# Oscillator_16MHz.net
KiCad netlist of a schematic drawn in Altium Designer
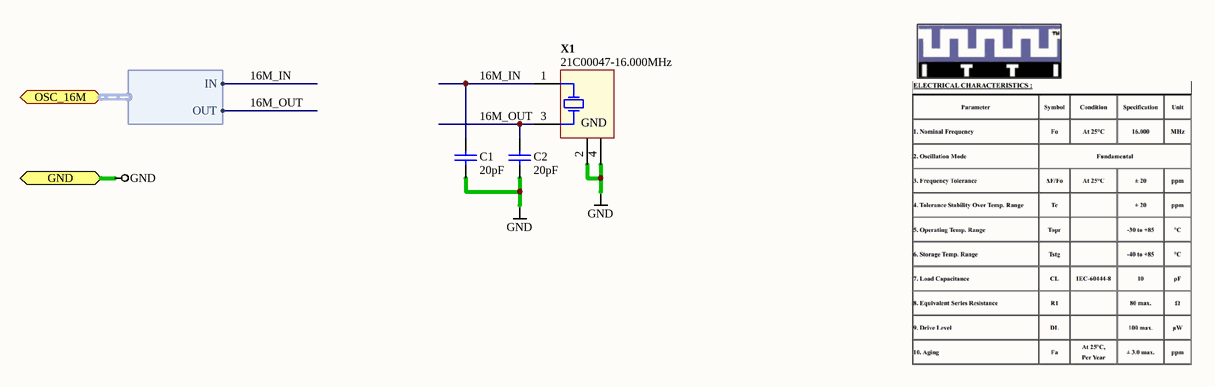
[diagram p0: Oscillator_16MHz.SchDoc]

(export (version "E")
  (design (tool "Eeschema 10.0.6"))
  (components
    (comp (ref "C1")
      (value "20pF")
      (footprint "CAPC0402(1005)60_N")
      (description "CAP 20pF 10V ±0.25pF 0402 (1005 Metric) Thickness 0.6mm SMD")
      (fields (field (name "TOLERANCE") "±0.25pF") (field (name "Comment") "CAP 20pF 10V 0402(1005)"))
      (libsource (lib "Altium Content Vault") (part "CMP-1034-00871-1"))
    )
    (comp (ref "C2")
      (value "20pF")
      (footprint "CAPC0402(1005)60_N")
      (description "CAP 20pF 10V ±0.25pF 0402 (1005 Metric) Thickness 0.6mm SMD")
      (fields (field (name "TOLERANCE") "±0.25pF") (field (name "Comment") "CAP 20pF 10V 0402(1005)"))
      (libsource (lib "Altium Content Vault") (part "CMP-1034-00871-1"))
    )
    (comp (ref "X1")
      (value "21C00047-16.000MHz")
      (footprint "ITTI-21C00047-16.000MHz-4_V")
      (description "Crystal, 16 MHz, -30 to 85 degC, 3.2 x 2.5 x 0.9 mm SMD")
      (fields (field (name "MANUFACTURER") "ITTI"))
      (libsource (lib "Altium Content Vault") (part "ITTI-21C00047-4"))
    )
  )
  (nets
    (net (code "2") (name "/16M_IN") (class "Default")
      (node (ref "C1") (pin "1") (pinfunction "1_1") (pintype "passive"))
      (node (ref "X1") (pin "1") (pinfunction "XTAL_1") (pintype "passive"))
    )
    (net (code "3") (name "/16M_OUT") (class "Default")
      (node (ref "C2") (pin "1") (pinfunction "1_1") (pintype "passive"))
      (node (ref "X1") (pin "3") (pinfunction "XTAL_3") (pintype "passive"))
    )
    (net (code "5") (name "GND") (class "Default")
      (node (ref "C1") (pin "2") (pinfunction "2_2") (pintype "passive"))
      (node (ref "C2") (pin "2") (pinfunction "2_2") (pintype "passive"))
      (node (ref "X1") (pin "2") (pinfunction "GND_2") (pintype "power_in"))
      (node (ref "X1") (pin "4") (pinfunction "GND_4") (pintype "power_in"))
    )
  )
)
